# atmega.net
KiCad netlist of a schematic drawn in Altium Designer
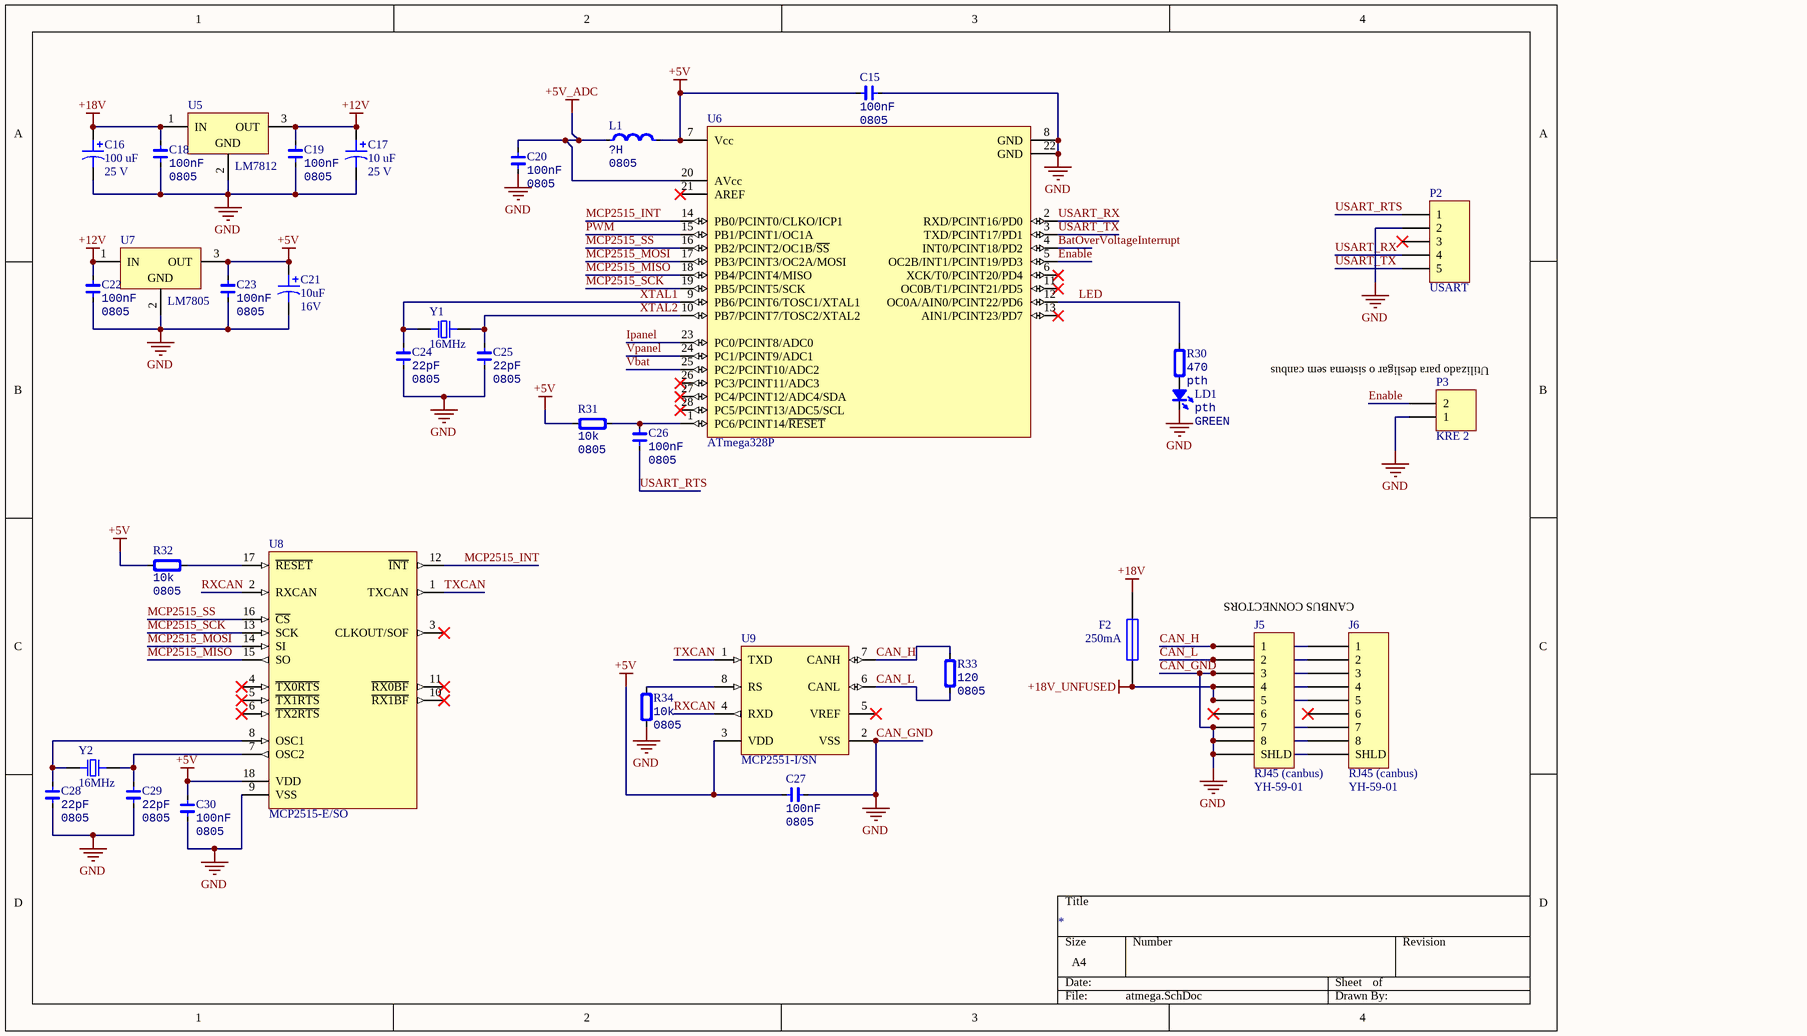
[diagram p0: atmega.SchDoc]

(export (version "E")
  (design (tool "Eeschema 10.0.6"))
  (components
    (comp (ref "C15")
      (value "100nF")
      (footprint "0805C")
      (description "Capacitor")
      (fields (field (name "TYPE") "0805"))
      (libsource (lib "") (part "Cap_0805_2"))
    )
    (comp (ref "C16")
      (value "100 uF")
      (footprint "cap10uF16V")
      (description "Solid Aluminum Capacitor with Organic Semiconductor Electrolyte: 100uF, 10V, Bulk Pack")
      (fields (field (name "VOLTAGE") "25 V") (field (name "Comment") "CapacitorPol"))
      (libsource (lib "R2R - Nova") (part "CapacitorPol"))
    )
    (comp (ref "C17")
      (value "10 uF")
      (footprint "cap10uF16V")
      (description "Solid Aluminum Capacitor with Organic Semiconductor Electrolyte: 100uF, 10V, Bulk Pack")
      (fields (field (name "VOLTAGE") "25 V") (field (name "Comment") "CapacitorPol"))
      (libsource (lib "R2R - Nova") (part "CapacitorPol"))
    )
    (comp (ref "C18")
      (value "100nF")
      (footprint "0805C")
      (description "Capacitor")
      (fields (field (name "TYPE") "0805"))
      (libsource (lib "SCH_Passive") (part "Cap_0805"))
    )
    (comp (ref "C19")
      (value "100nF")
      (footprint "0805C")
      (description "Capacitor")
      (fields (field (name "TYPE") "0805"))
      (libsource (lib "SCH_Passive") (part "Cap_0805"))
    )
    (comp (ref "C20")
      (value "100nF")
      (footprint "0805C")
      (description "Capacitor")
      (fields (field (name "TYPE") "0805"))
      (libsource (lib "SCH_Passive") (part "Cap_0805"))
    )
    (comp (ref "C21")
      (value "10uF")
      (footprint "cap10uF16V")
      (description "Solid Aluminum Capacitor with Organic Semiconductor Electrolyte: 100uF, 10V, Bulk Pack")
      (fields (field (name "VOLTAGE") "16V") (field (name "Comment") "CapacitorPol"))
      (libsource (lib "R2R - Nova") (part "CapacitorPol"))
    )
    (comp (ref "C22")
      (value "100nF")
      (footprint "0805C")
      (description "Capacitor")
      (fields (field (name "TYPE") "0805"))
      (libsource (lib "SCH_Passive") (part "Cap_0805"))
    )
    (comp (ref "C23")
      (value "100nF")
      (footprint "0805C")
      (description "Capacitor")
      (fields (field (name "TYPE") "0805"))
      (libsource (lib "SCH_Passive") (part "Cap_0805"))
    )
    (comp (ref "C24")
      (value "22pF")
      (footprint "0805C")
      (description "Capacitor")
      (fields (field (name "TYPE") "0805"))
      (libsource (lib "SCH_Passive") (part "Cap_0805"))
    )
    (comp (ref "C25")
      (value "22pF")
      (footprint "0805C")
      (description "Capacitor")
      (fields (field (name "TYPE") "0805"))
      (libsource (lib "SCH_Passive") (part "Cap_0805"))
    )
    (comp (ref "C26")
      (value "100nF")
      (footprint "0805C")
      (description "Capacitor")
      (fields (field (name "TYPE") "0805"))
      (libsource (lib "") (part "Cap_0805_1"))
    )
    (comp (ref "C27")
      (value "100nF")
      (footprint "0805C")
      (description "Capacitor")
      (fields (field (name "TYPE") "0805"))
      (libsource (lib "") (part "Cap_0805_2"))
    )
    (comp (ref "C28")
      (value "22pF")
      (footprint "0805C")
      (description "Capacitor")
      (fields (field (name "TYPE") "0805"))
      (libsource (lib "SCH_Passive") (part "Cap_0805"))
    )
    (comp (ref "C29")
      (value "22pF")
      (footprint "0805C")
      (description "Capacitor")
      (fields (field (name "TYPE") "0805"))
      (libsource (lib "SCH_Passive") (part "Cap_0805"))
    )
    (comp (ref "C30")
      (value "100nF")
      (footprint "0805C")
      (description "Capacitor")
      (fields (field (name "TYPE") "0805"))
      (libsource (lib "") (part "Cap_0805_1"))
    )
    (comp (ref "F2")
      (value "250mA")
      (footprint "Porta Fusivel")
      (description "Fuse")
      (libsource (lib "Miscellaneous Devices") (part "Fuse 1"))
    )
    (comp (ref "J5")
      (value "RJ45 (canbus)")
      (footprint "ASSMANN A-2004-2-4-LP/FS")
      (description "YH-59-01")
      (fields (field (name "ALTIUM_VALUE") "YH-59-01"))
      (libsource (lib "Connectors") (part "Modular Jack with Shield"))
    )
    (comp (ref "J6")
      (value "RJ45 (canbus)")
      (footprint "ASSMANN A-2004-2-4-LP/FS")
      (description "YH-59-01")
      (fields (field (name "ALTIUM_VALUE") "YH-59-01"))
      (libsource (lib "Connectors") (part "Modular Jack with Shield"))
    )
    (comp (ref "L1")
      (value "?H")
      (footprint "Zenite_Footprints:0805L")
      (description "Inductor")
      (fields (field (name "TYPE") "0805"))
      (libsource (lib "SCH_Passive") (part "Ind_0805"))
    )
    (comp (ref "LD1")
      (value "GREEN")
      (footprint "LED3MM")
      (description "LED")
      (fields (field (name "TYPE") "pth"))
      (libsource (lib "SCH_Active") (part "LED_0805"))
    )
    (comp (ref "P2")
      (value "USART")
      (footprint "HDR1X5")
      (description "Header, 5-Pin")
      (libsource (lib "R2R - Nova") (part "Header 5"))
    )
    (comp (ref "P3")
      (value "KRE 2")
      (footprint "KRE_2")
      (description "Terminal Block 1x2")
      (libsource (lib "R2R - Nova") (part "KRE_2"))
    )
    (comp (ref "R30")
      (value "470")
      (footprint "AXIAL-0.3")
      (description "Resistor")
      (fields (field (name "TYPE") "pth"))
      (libsource (lib "SCH_Passive") (part "Res_0805"))
    )
    (comp (ref "R31")
      (value "10k")
      (footprint "0805R")
      (description "Resistor")
      (fields (field (name "TYPE") "0805"))
      (libsource (lib "SCH_Passive") (part "Res_0805"))
    )
    (comp (ref "R32")
      (value "10k")
      (footprint "0805R")
      (description "Resistor")
      (fields (field (name "TYPE") "0805"))
      (libsource (lib "SCH_Passive") (part "Res_0805"))
    )
    (comp (ref "R33")
      (value "120")
      (footprint "0805R")
      (description "Resistor")
      (fields (field (name "TYPE") "0805"))
      (libsource (lib "SCH_Passive") (part "Res_0805"))
    )
    (comp (ref "R34")
      (value "10k")
      (footprint "0805R")
      (description "Resistor")
      (fields (field (name "TYPE") "0805"))
      (libsource (lib "SCH_Passive") (part "Res_0805"))
    )
    (comp (ref "U5")
      (value "LM7812")
      (footprint "TO220_deitado")
      (description "Positive-Voltage Regulator")
      (libsource (lib "TI Power Mgt Voltage Regulator") (part "µA7805CKC"))
    )
    (comp (ref "U6")
      (value "ATmega328P")
      (footprint "DIP28-300(100)")
      (libsource (lib "R2R - Nova") (part "ATmega328P"))
    )
    (comp (ref "U7")
      (value "LM7805")
      (footprint "TO220_deitado")
      (description "Positive-Voltage Regulator")
      (libsource (lib "TI Power Mgt Voltage Regulator") (part "µA7805CKC"))
    )
    (comp (ref "U8")
      (value "MCP2515-E/SO")
      (footprint "WSO18_L")
      (description "Stand-Alone CAN Controller With SPI Interface, 18-Pin SOIC, Extended Temperature")
      (libsource (lib "Altium Content Vault") (part "COM-CAN-MCP2515-18"))
    )
    (comp (ref "U9")
      (value "MCP2551-I/SN")
      (footprint "SOIC08-150(50)")
      (libsource (lib "Altium Content Vault") (part "MCHP-MCP2551-SN8"))
    )
    (comp (ref "Y1")
      (value "16MHz")
      (footprint "HC49-US-THT")
      (description "Crystal")
      (libsource (lib "R2R - Nova") (part "Crystal"))
    )
    (comp (ref "Y2")
      (value "16MHz")
      (footprint "HC49-US-THT")
      (description "Crystal")
      (libsource (lib "R2R - Nova") (part "Crystal"))
    )
  )
  (nets
    (net (code "1") (name "+5V") (class "Default")
      (node (ref "C15") (pin "1") (pinfunction "1_1") (pintype "passive"))
      (node (ref "C21") (pin "1") (pinfunction "1_1") (pintype "passive"))
      (node (ref "C23") (pin "2") (pinfunction "2_2") (pintype "passive"))
      (node (ref "C27") (pin "1") (pinfunction "1_1") (pintype "passive"))
      (node (ref "C30") (pin "1") (pinfunction "1_1") (pintype "passive"))
      (node (ref "L1") (pin "2") (pinfunction "2_2") (pintype "passive"))
      (node (ref "R31") (pin "1") (pinfunction "1_1") (pintype "passive"))
      (node (ref "R32") (pin "1") (pinfunction "1_1") (pintype "passive"))
      (node (ref "U6") (pin "7") (pinfunction "Vcc_7") (pintype "passive"))
      (node (ref "U7") (pin "3") (pinfunction "OUT_3") (pintype "power_in"))
      (node (ref "U8") (pin "18") (pinfunction "VDD_18") (pintype "power_in"))
      (node (ref "U9") (pin "3") (pinfunction "VDD_3") (pintype "power_in"))
    )
    (net (code "2") (name "+5V_ADC") (class "Default")
      (node (ref "C20") (pin "2") (pinfunction "2_2") (pintype "passive"))
      (node (ref "L1") (pin "1") (pinfunction "1_1") (pintype "passive"))
      (node (ref "U6") (pin "20") (pinfunction "AVcc_20") (pintype "passive"))
    )
    (net (code "3") (name "+12V") (class "Default")
      (node (ref "C17") (pin "1") (pinfunction "1_1") (pintype "passive"))
      (node (ref "C19") (pin "2") (pinfunction "2_2") (pintype "passive"))
      (node (ref "C22") (pin "2") (pinfunction "2_2") (pintype "passive"))
      (node (ref "U5") (pin "3") (pinfunction "OUT_3") (pintype "power_in"))
      (node (ref "U7") (pin "1") (pinfunction "IN_1") (pintype "power_in"))
    )
    (net (code "4") (name "+18V") (class "Default")
      (node (ref "C16") (pin "1") (pinfunction "1_1") (pintype "passive"))
      (node (ref "C18") (pin "2") (pinfunction "2_2") (pintype "passive"))
      (node (ref "F2") (pin "1") (pinfunction "1_1") (pintype "passive"))
      (node (ref "U5") (pin "1") (pinfunction "IN_1") (pintype "power_in"))
    )
    (net (code "5") (name "+18V_UNFUSED") (class "Default")
      (node (ref "F2") (pin "2") (pinfunction "2_2") (pintype "passive"))
      (node (ref "J5") (pin "4") (pinfunction "4_4") (pintype "passive"))
      (node (ref "J5") (pin "5") (pinfunction "5_5") (pintype "passive"))
      (node (ref "J6") (pin "4") (pinfunction "4_4") (pintype "passive"))
      (node (ref "J6") (pin "5") (pinfunction "5_5") (pintype "passive"))
    )
    (net (code "6") (name "/BatOverVoltageInterrupt") (class "Default")
      (node (ref "U6") (pin "4") (pinfunction "INT0/PCINT18/PD2_4") (pintype "bidirectional"))
    )
    (net (code "7") (name "/CAN_H") (class "Default")
      (node (ref "J5") (pin "1") (pinfunction "1_1") (pintype "passive"))
      (node (ref "J6") (pin "1") (pinfunction "1_1") (pintype "passive"))
      (node (ref "R33") (pin "2") (pinfunction "2_2") (pintype "passive"))
      (node (ref "U9") (pin "7") (pinfunction "CANH_7") (pintype "bidirectional"))
    )
    (net (code "8") (name "/CAN_L") (class "Default")
      (node (ref "J5") (pin "2") (pinfunction "2_2") (pintype "passive"))
      (node (ref "J6") (pin "2") (pinfunction "2_2") (pintype "passive"))
      (node (ref "R33") (pin "1") (pinfunction "1_1") (pintype "passive"))
      (node (ref "U9") (pin "6") (pinfunction "CANL_6") (pintype "bidirectional"))
    )
    (net (code "9") (name "/Enable") (class "Default")
      (node (ref "P3") (pin "2") (pinfunction "2_2") (pintype "passive"))
      (node (ref "U6") (pin "5") (pinfunction "OC2B/INT1/PCINT19/PD3_5") (pintype "bidirectional"))
    )
    (net (code "10") (name "/Ipanel") (class "Default")
      (node (ref "U6") (pin "23") (pinfunction "PC0/PCINT8/ADC0_23") (pintype "bidirectional"))
    )
    (net (code "11") (name "/LED") (class "Default")
      (node (ref "R30") (pin "2") (pinfunction "2_2") (pintype "passive"))
      (node (ref "U6") (pin "12") (pinfunction "OC0A/AIN0/PCINT22/PD6_12") (pintype "bidirectional"))
    )
    (net (code "12") (name "/MCP2515_INT") (class "Default")
      (node (ref "U6") (pin "14") (pinfunction "PB0/PCINT0/CLKO/ICP1_14") (pintype "bidirectional"))
      (node (ref "U8") (pin "12") (pinfunction "~{INT}_12") (pintype "output"))
    )
    (net (code "13") (name "/MCP2515_MISO") (class "Default")
      (node (ref "U6") (pin "18") (pinfunction "PB4/PCINT4/MISO_18") (pintype "bidirectional"))
      (node (ref "U8") (pin "15") (pinfunction "SO_15") (pintype "output"))
    )
    (net (code "14") (name "/MCP2515_MOSI") (class "Default")
      (node (ref "U6") (pin "17") (pinfunction "PB3/PCINT3/OC2A/MOSI_17") (pintype "bidirectional"))
      (node (ref "U8") (pin "14") (pinfunction "SI_14") (pintype "input"))
    )
    (net (code "15") (name "/MCP2515_SCK") (class "Default")
      (node (ref "U6") (pin "19") (pinfunction "PB5/PCINT5/SCK_19") (pintype "bidirectional"))
      (node (ref "U8") (pin "13") (pinfunction "SCK_13") (pintype "input"))
    )
    (net (code "16") (name "/MCP2515_SS") (class "Default")
      (node (ref "U6") (pin "16") (pinfunction "PB2/PCINT2/OC1B/~{SS}_16") (pintype "bidirectional"))
      (node (ref "U8") (pin "16") (pinfunction "~{CS}_16") (pintype "input"))
    )
    (net (code "17") (name "/PWM") (class "Default")
      (node (ref "U6") (pin "15") (pinfunction "PB1/PCINT1/OC1A_15") (pintype "bidirectional"))
    )
    (net (code "18") (name "/RXCAN") (class "Default")
      (node (ref "U8") (pin "2") (pinfunction "RXCAN_2") (pintype "input"))
      (node (ref "U9") (pin "4") (pinfunction "RXD_4") (pintype "output"))
    )
    (net (code "19") (name "/TXCAN") (class "Default")
      (node (ref "U8") (pin "1") (pinfunction "TXCAN_1") (pintype "output"))
      (node (ref "U9") (pin "1") (pinfunction "TXD_1") (pintype "input"))
    )
    (net (code "20") (name "/USART_RTS") (class "Default")
      (node (ref "C26") (pin "2") (pinfunction "2_2") (pintype "passive"))
      (node (ref "P2") (pin "1") (pinfunction "1_1") (pintype "passive"))
    )
    (net (code "21") (name "/USART_RX") (class "Default")
      (node (ref "P2") (pin "4") (pinfunction "4_4") (pintype "passive"))
      (node (ref "U6") (pin "2") (pinfunction "RXD/PCINT16/PD0_2") (pintype "bidirectional"))
    )
    (net (code "22") (name "/USART_TX") (class "Default")
      (node (ref "P2") (pin "5") (pinfunction "5_5") (pintype "passive"))
      (node (ref "U6") (pin "3") (pinfunction "TXD/PCINT17/PD1_3") (pintype "bidirectional"))
    )
    (net (code "23") (name "/Vbat") (class "Default")
      (node (ref "U6") (pin "25") (pinfunction "PC2/PCINT10/ADC2_25") (pintype "bidirectional"))
    )
    (net (code "24") (name "/Vpanel") (class "Default")
      (node (ref "U6") (pin "24") (pinfunction "PC1/PCINT9/ADC1_24") (pintype "bidirectional"))
    )
    (net (code "25") (name "/XTAL1") (class "Default")
      (node (ref "C24") (pin "2") (pinfunction "2_2") (pintype "passive"))
      (node (ref "U6") (pin "9") (pinfunction "PB6/PCINT6/TOSC1/XTAL1_9") (pintype "bidirectional"))
      (node (ref "Y1") (pin "1") (pinfunction "1_1") (pintype "passive"))
    )
    (net (code "26") (name "/XTAL2") (class "Default")
      (node (ref "C25") (pin "2") (pinfunction "2_2") (pintype "passive"))
      (node (ref "U6") (pin "10") (pinfunction "PB7/PCINT7/TOSC2/XTAL2_10") (pintype "bidirectional"))
      (node (ref "Y1") (pin "2") (pinfunction "2_2") (pintype "passive"))
    )
    (net (code "27") (name "GND") (class "Default")
      (node (ref "C15") (pin "2") (pinfunction "2_2") (pintype "passive"))
      (node (ref "C16") (pin "2") (pinfunction "2_2") (pintype "passive"))
      (node (ref "C17") (pin "2") (pinfunction "2_2") (pintype "passive"))
      (node (ref "C18") (pin "1") (pinfunction "1_1") (pintype "passive"))
      (node (ref "C19") (pin "1") (pinfunction "1_1") (pintype "passive"))
      (node (ref "C20") (pin "1") (pinfunction "1_1") (pintype "passive"))
      (node (ref "C21") (pin "2") (pinfunction "2_2") (pintype "passive"))
      (node (ref "C22") (pin "1") (pinfunction "1_1") (pintype "passive"))
      (node (ref "C23") (pin "1") (pinfunction "1_1") (pintype "passive"))
      (node (ref "C24") (pin "1") (pinfunction "1_1") (pintype "passive"))
      (node (ref "C25") (pin "1") (pinfunction "1_1") (pintype "passive"))
      (node (ref "C27") (pin "2") (pinfunction "2_2") (pintype "passive"))
      (node (ref "C28") (pin "1") (pinfunction "1_1") (pintype "passive"))
      (node (ref "C29") (pin "1") (pinfunction "1_1") (pintype "passive"))
      (node (ref "C30") (pin "2") (pinfunction "2_2") (pintype "passive"))
      (node (ref "J5") (pin "3") (pinfunction "3_3") (pintype "passive"))
      (node (ref "J5") (pin "7") (pinfunction "7_7") (pintype "passive"))
      (node (ref "J5") (pin "8") (pinfunction "8_8") (pintype "passive"))
      (node (ref "J5") (pin "S") (pinfunction "SHLD_S") (pintype "passive"))
      (node (ref "J6") (pin "3") (pinfunction "3_3") (pintype "passive"))
      (node (ref "J6") (pin "7") (pinfunction "7_7") (pintype "passive"))
      (node (ref "J6") (pin "8") (pinfunction "8_8") (pintype "passive"))
      (node (ref "J6") (pin "S") (pinfunction "SHLD_S") (pintype "passive"))
      (node (ref "LD1") (pin "2") (pinfunction "K_2") (pintype "passive"))
      (node (ref "P2") (pin "2") (pinfunction "2_2") (pintype "passive"))
      (node (ref "P3") (pin "1") (pinfunction "1_1") (pintype "passive"))
      (node (ref "R34") (pin "2") (pinfunction "2_2") (pintype "passive"))
      (node (ref "U5") (pin "2") (pinfunction "GND_2") (pintype "power_in"))
      (node (ref "U6") (pin "22") (pinfunction "GND_22") (pintype "passive"))
      (node (ref "U6") (pin "8") (pinfunction "GND_8") (pintype "passive"))
      (node (ref "U7") (pin "2") (pinfunction "GND_2") (pintype "power_in"))
      (node (ref "U8") (pin "9") (pinfunction "VSS_9") (pintype "power_in"))
      (node (ref "U9") (pin "2") (pinfunction "VSS_2") (pintype "power_in"))
    )
    (net (code "28") (name "Net-(LD1-A)") (class "Default")
      (node (ref "LD1") (pin "1") (pinfunction "A_1") (pintype "passive"))
      (node (ref "R30") (pin "1") (pinfunction "1_1") (pintype "passive"))
    )
    (net (code "29") (name "Net-(U6-PC6{slash}PCINT14{slash}~{RESET})") (class "Default")
      (node (ref "C26") (pin "1") (pinfunction "1_1") (pintype "passive"))
      (node (ref "R31") (pin "2") (pinfunction "2_2") (pintype "passive"))
      (node (ref "U6") (pin "1") (pinfunction "PC6/PCINT14/~{RESET}_1") (pintype "bidirectional"))
    )
    (net (code "30") (name "Net-(U8-OSC1)") (class "Default")
      (node (ref "C28") (pin "2") (pinfunction "2_2") (pintype "passive"))
      (node (ref "U8") (pin "8") (pinfunction "OSC1_8") (pintype "input"))
      (node (ref "Y2") (pin "1") (pinfunction "1_1") (pintype "passive"))
    )
    (net (code "31") (name "Net-(U8-OSC2)") (class "Default")
      (node (ref "C29") (pin "2") (pinfunction "2_2") (pintype "passive"))
      (node (ref "U8") (pin "7") (pinfunction "OSC2_7") (pintype "output"))
      (node (ref "Y2") (pin "2") (pinfunction "2_2") (pintype "passive"))
    )
    (net (code "32") (name "Net-(U8-~{RESET})") (class "Default")
      (node (ref "R32") (pin "2") (pinfunction "2_2") (pintype "passive"))
      (node (ref "U8") (pin "17") (pinfunction "~{RESET}_17") (pintype "input"))
    )
    (net (code "33") (name "Net-(U9-RS)") (class "Default")
      (node (ref "R34") (pin "1") (pinfunction "1_1") (pintype "passive"))
      (node (ref "U9") (pin "8") (pinfunction "RS_8") (pintype "input"))
    )
    (net (code "34") (name "unconnected-(J5-Pad6)") (class "Default")
      (node (ref "J5") (pin "6") (pinfunction "6_6") (pintype "passive+no_connect"))
    )
    (net (code "35") (name "unconnected-(J6-Pad6)") (class "Default")
      (node (ref "J6") (pin "6") (pinfunction "6_6") (pintype "passive+no_connect"))
    )
    (net (code "36") (name "unconnected-(P2-Pad3)") (class "Default")
      (node (ref "P2") (pin "3") (pinfunction "3_3") (pintype "passive+no_connect"))
    )
    (net (code "37") (name "unconnected-(U6-AIN1{slash}PCINT23{slash}PD7-Pad13)") (class "Default")
      (node (ref "U6") (pin "13") (pinfunction "AIN1/PCINT23/PD7_13") (pintype "bidirectional+no_connect"))
    )
    (net (code "38") (name "unconnected-(U6-AREF-Pad21)") (class "Default")
      (node (ref "U6") (pin "21") (pinfunction "AREF_21") (pintype "passive+no_connect"))
    )
    (net (code "39") (name "unconnected-(U6-OC0B{slash}T1{slash}PCINT21{slash}PD5-Pad11)") (class "Default")
      (node (ref "U6") (pin "11") (pinfunction "OC0B/T1/PCINT21/PD5_11") (pintype "bidirectional+no_connect"))
    )
    (net (code "40") (name "unconnected-(U6-PC3{slash}PCINT11{slash}ADC3-Pad26)") (class "Default")
      (node (ref "U6") (pin "26") (pinfunction "PC3/PCINT11/ADC3_26") (pintype "bidirectional+no_connect"))
    )
    (net (code "41") (name "unconnected-(U6-PC4{slash}PCINT12{slash}ADC4{slash}SDA-Pad27)") (class "Default")
      (node (ref "U6") (pin "27") (pinfunction "PC4/PCINT12/ADC4/SDA_27") (pintype "bidirectional+no_connect"))
    )
    (net (code "42") (name "unconnected-(U6-PC5{slash}PCINT13{slash}ADC5{slash}SCL-Pad28)") (class "Default")
      (node (ref "U6") (pin "28") (pinfunction "PC5/PCINT13/ADC5/SCL_28") (pintype "bidirectional+no_connect"))
    )
    (net (code "43") (name "unconnected-(U6-XCK{slash}T0{slash}PCINT20{slash}PD4-Pad6)") (class "Default")
      (node (ref "U6") (pin "6") (pinfunction "XCK/T0/PCINT20/PD4_6") (pintype "bidirectional+no_connect"))
    )
    (net (code "44") (name "unconnected-(U8-CLKOUT{slash}SOF-Pad3)") (class "Default")
      (node (ref "U8") (pin "3") (pinfunction "CLKOUT/SOF_3") (pintype "output+no_connect"))
    )
    (net (code "45") (name "unconnected-(U8-~{RX0BF}-Pad11)") (class "Default")
      (node (ref "U8") (pin "11") (pinfunction "~{RX0BF}_11") (pintype "output+no_connect"))
    )
    (net (code "46") (name "unconnected-(U8-~{RX1BF}-Pad10)") (class "Default")
      (node (ref "U8") (pin "10") (pinfunction "~{RX1BF}_10") (pintype "output+no_connect"))
    )
    (net (code "47") (name "unconnected-(U8-~{TX0RTS}-Pad4)") (class "Default")
      (node (ref "U8") (pin "4") (pinfunction "~{TX0RTS}_4") (pintype "input+no_connect"))
    )
    (net (code "48") (name "unconnected-(U8-~{TX1RTS}-Pad5)") (class "Default")
      (node (ref "U8") (pin "5") (pinfunction "~{TX1RTS}_5") (pintype "input+no_connect"))
    )
    (net (code "49") (name "unconnected-(U8-~{TX2RTS}-Pad6)") (class "Default")
      (node (ref "U8") (pin "6") (pinfunction "~{TX2RTS}_6") (pintype "input+no_connect"))
    )
    (net (code "50") (name "unconnected-(U9-VREF-Pad5)") (class "Default")
      (node (ref "U9") (pin "5") (pinfunction "VREF_5") (pintype "power_in+no_connect"))
    )
  )
)
